# Servo555.net
KiCad netlist of a schematic drawn in EAGLE
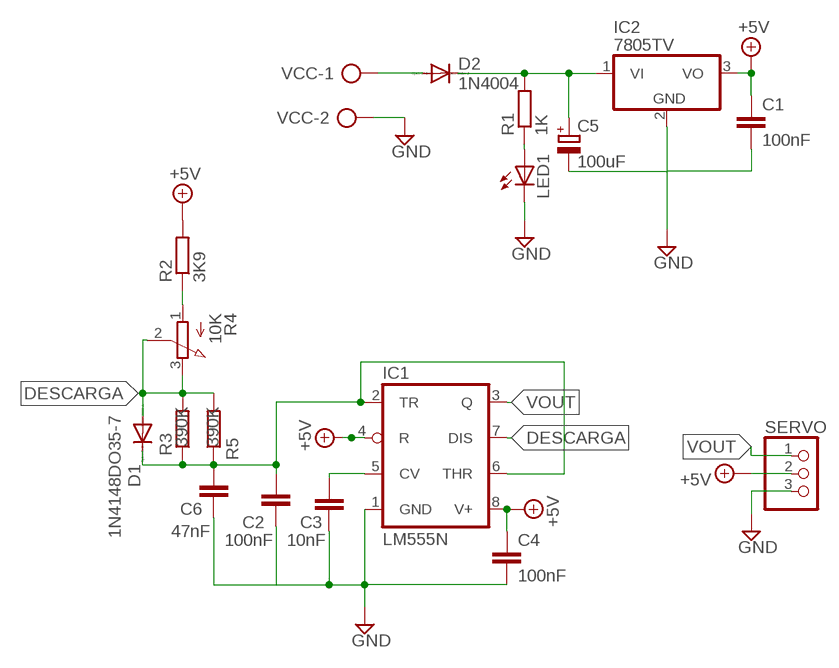
[diagram p0: schematic, sheet 1]

(export (version "E")
  (design (tool "Eeschema 10.0.6"))
  (components
    (comp (ref "C1")
      (value "100nF")
      (footprint "eagle-import:C050-025X075")
      (libsource (lib "eagle-import") (part "C-EU050-025X075"))
    )
    (comp (ref "C2")
      (value "100nF")
      (footprint "eagle-import:C050-025X075")
      (libsource (lib "eagle-import") (part "C-EU050-025X075"))
    )
    (comp (ref "C3")
      (value "10nF")
      (footprint "eagle-import:C050-025X075")
      (libsource (lib "eagle-import") (part "C-EU050-025X075"))
    )
    (comp (ref "C4")
      (value "100nF")
      (footprint "eagle-import:C050-025X075")
      (libsource (lib "eagle-import") (part "C-EU050-025X075"))
    )
    (comp (ref "C5")
      (value "100uF")
      (footprint "eagle-import:E2,5-7")
      (libsource (lib "eagle-import") (part "CPOL-EUE2.5-7"))
    )
    (comp (ref "C6")
      (value "47nF")
      (footprint "eagle-import:C050-025X075")
      (libsource (lib "eagle-import") (part "C-EU050-025X075"))
    )
    (comp (ref "D1")
      (value "1N4148DO35-7")
      (footprint "eagle-import:DO35-7")
      (libsource (lib "eagle-import") (part "1N4148DO35-7"))
    )
    (comp (ref "D2")
      (value "1N4004")
      (footprint "eagle-import:DO41-10")
      (libsource (lib "eagle-import") (part "1N4004"))
    )
    (comp (ref "IC1")
      (value "LM555N")
      (footprint "eagle-import:DIL08")
      (libsource (lib "eagle-import") (part "555NLM"))
    )
    (comp (ref "IC2")
      (value "7805TV")
      (footprint "eagle-import:TO220V")
      (libsource (lib "eagle-import") (part "78TV05"))
    )
    (comp (ref "LED1")
      (value "LED3MM")
      (footprint "eagle-import:LED3MM")
      (libsource (lib "eagle-import") (part "LED3MM"))
    )
    (comp (ref "R1")
      (value "1K")
      (footprint "eagle-import:0207_7")
      (libsource (lib "eagle-import") (part "R-EU_0207/7"))
    )
    (comp (ref "R2")
      (value "3K9")
      (footprint "eagle-import:0207_7")
      (libsource (lib "eagle-import") (part "R-EU_0207/7"))
    )
    (comp (ref "R3")
      (value "390K")
      (footprint "eagle-import:0207_7")
      (libsource (lib "eagle-import") (part "R-EU_0207/7"))
    )
    (comp (ref "R4")
      (value "10K")
      (footprint "eagle-import:3RP_1610N")
      (libsource (lib "eagle-import") (part "3RP/1610N"))
    )
    (comp (ref "R5")
      (value "390K")
      (footprint "eagle-import:0207_7")
      (libsource (lib "eagle-import") (part "R-EU_0207/7"))
    )
    (comp (ref "SERVO")
      (value "PINHD-1X3")
      (footprint "eagle-import:1X03")
      (libsource (lib "eagle-import") (part "PINHD-1X3"))
    )
    (comp (ref "VCC")
      (value "AK500/2")
      (footprint "eagle-import:AK500_2")
      (libsource (lib "eagle-import") (part "AK500/2"))
    )
  )
  (nets
    (net (code "1") (name "+5V") (class "Default")
      (node (ref "C1") (pin "1") (pinfunction "1_1") (pintype "passive"))
      (node (ref "C4") (pin "1") (pinfunction "1_1") (pintype "passive"))
      (node (ref "IC1") (pin "4") (pinfunction "R_4") (pintype "input"))
      (node (ref "IC1") (pin "8") (pinfunction "V+_8") (pintype "power_in"))
      (node (ref "IC2") (pin "3") (pinfunction "VO_3") (pintype "passive"))
      (node (ref "R2") (pin "2") (pinfunction "2_2") (pintype "passive"))
      (node (ref "SERVO") (pin "2") (pinfunction "2_2") (pintype "passive"))
    )
    (net (code "2") (name "DESCARGA") (class "Default")
      (node (ref "D1") (pin "A") (pinfunction "A_A") (pintype "passive"))
      (node (ref "IC1") (pin "7") (pinfunction "DIS_7") (pintype "input"))
      (node (ref "R3") (pin "2") (pinfunction "2_2") (pintype "passive"))
      (node (ref "R4") (pin "2") (pinfunction "S_2") (pintype "passive"))
      (node (ref "R4") (pin "3") (pinfunction "E_3") (pintype "passive"))
      (node (ref "R5") (pin "2") (pinfunction "2_2") (pintype "passive"))
    )
    (net (code "3") (name "GND") (class "Default")
      (node (ref "C1") (pin "2") (pinfunction "2_2") (pintype "passive"))
      (node (ref "C2") (pin "2") (pinfunction "2_2") (pintype "passive"))
      (node (ref "C3") (pin "2") (pinfunction "2_2") (pintype "passive"))
      (node (ref "C4") (pin "2") (pinfunction "2_2") (pintype "passive"))
      (node (ref "C5") (pin "-") (pinfunction "-_-") (pintype "passive"))
      (node (ref "C6") (pin "2") (pinfunction "2_2") (pintype "passive"))
      (node (ref "IC1") (pin "1") (pinfunction "GND_1") (pintype "power_in"))
      (node (ref "IC2") (pin "2") (pinfunction "GND_2") (pintype "passive"))
      (node (ref "LED1") (pin "K") (pinfunction "C_K") (pintype "passive"))
      (node (ref "SERVO") (pin "3") (pinfunction "3_3") (pintype "passive"))
      (node (ref "VCC") (pin "2") (pinfunction "KL_2") (pintype "passive"))
    )
    (net (code "4") (name "Net-(IC1-CV)") (class "Default")
      (node (ref "C3") (pin "1") (pinfunction "1_1") (pintype "passive"))
      (node (ref "IC1") (pin "5") (pinfunction "CV_5") (pintype "input"))
    )
    (net (code "5") (name "Net-(IC1-THR)") (class "Default")
      (node (ref "C2") (pin "1") (pinfunction "1_1") (pintype "passive"))
      (node (ref "C6") (pin "1") (pinfunction "1_1") (pintype "passive"))
      (node (ref "D1") (pin "C") (pinfunction "C_C") (pintype "passive"))
      (node (ref "IC1") (pin "2") (pinfunction "TR_2") (pintype "input"))
      (node (ref "IC1") (pin "6") (pinfunction "THR_6") (pintype "input"))
      (node (ref "R3") (pin "1") (pinfunction "1_1") (pintype "passive"))
      (node (ref "R5") (pin "1") (pinfunction "1_1") (pintype "passive"))
    )
    (net (code "6") (name "Net-(IC2-VI)") (class "Default")
      (node (ref "C5") (pin "+") (pinfunction "+_+") (pintype "passive"))
      (node (ref "D2") (pin "C") (pinfunction "C_C") (pintype "passive"))
      (node (ref "IC2") (pin "1") (pinfunction "VI_1") (pintype "input"))
      (node (ref "R1") (pin "2") (pinfunction "2_2") (pintype "passive"))
    )
    (net (code "7") (name "Net-(LED1-PadA)") (class "Default")
      (node (ref "LED1") (pin "A") (pinfunction "A_A") (pintype "passive"))
      (node (ref "R1") (pin "1") (pinfunction "1_1") (pintype "passive"))
    )
    (net (code "8") (name "Net-(R4-A)") (class "Default")
      (node (ref "R2") (pin "1") (pinfunction "1_1") (pintype "passive"))
      (node (ref "R4") (pin "1") (pinfunction "A_1") (pintype "passive"))
    )
    (net (code "9") (name "Net-(VCCA-KL)") (class "Default")
      (node (ref "D2") (pin "A") (pinfunction "A_A") (pintype "passive"))
      (node (ref "VCC") (pin "1") (pinfunction "KL_1") (pintype "passive"))
    )
    (net (code "10") (name "VOUT") (class "Default")
      (node (ref "IC1") (pin "3") (pinfunction "Q_3") (pintype "output"))
      (node (ref "SERVO") (pin "1") (pinfunction "1_1") (pintype "passive"))
    )
  )
)
